# CC2530.net
KiCad netlist of a schematic drawn in Altium Designer
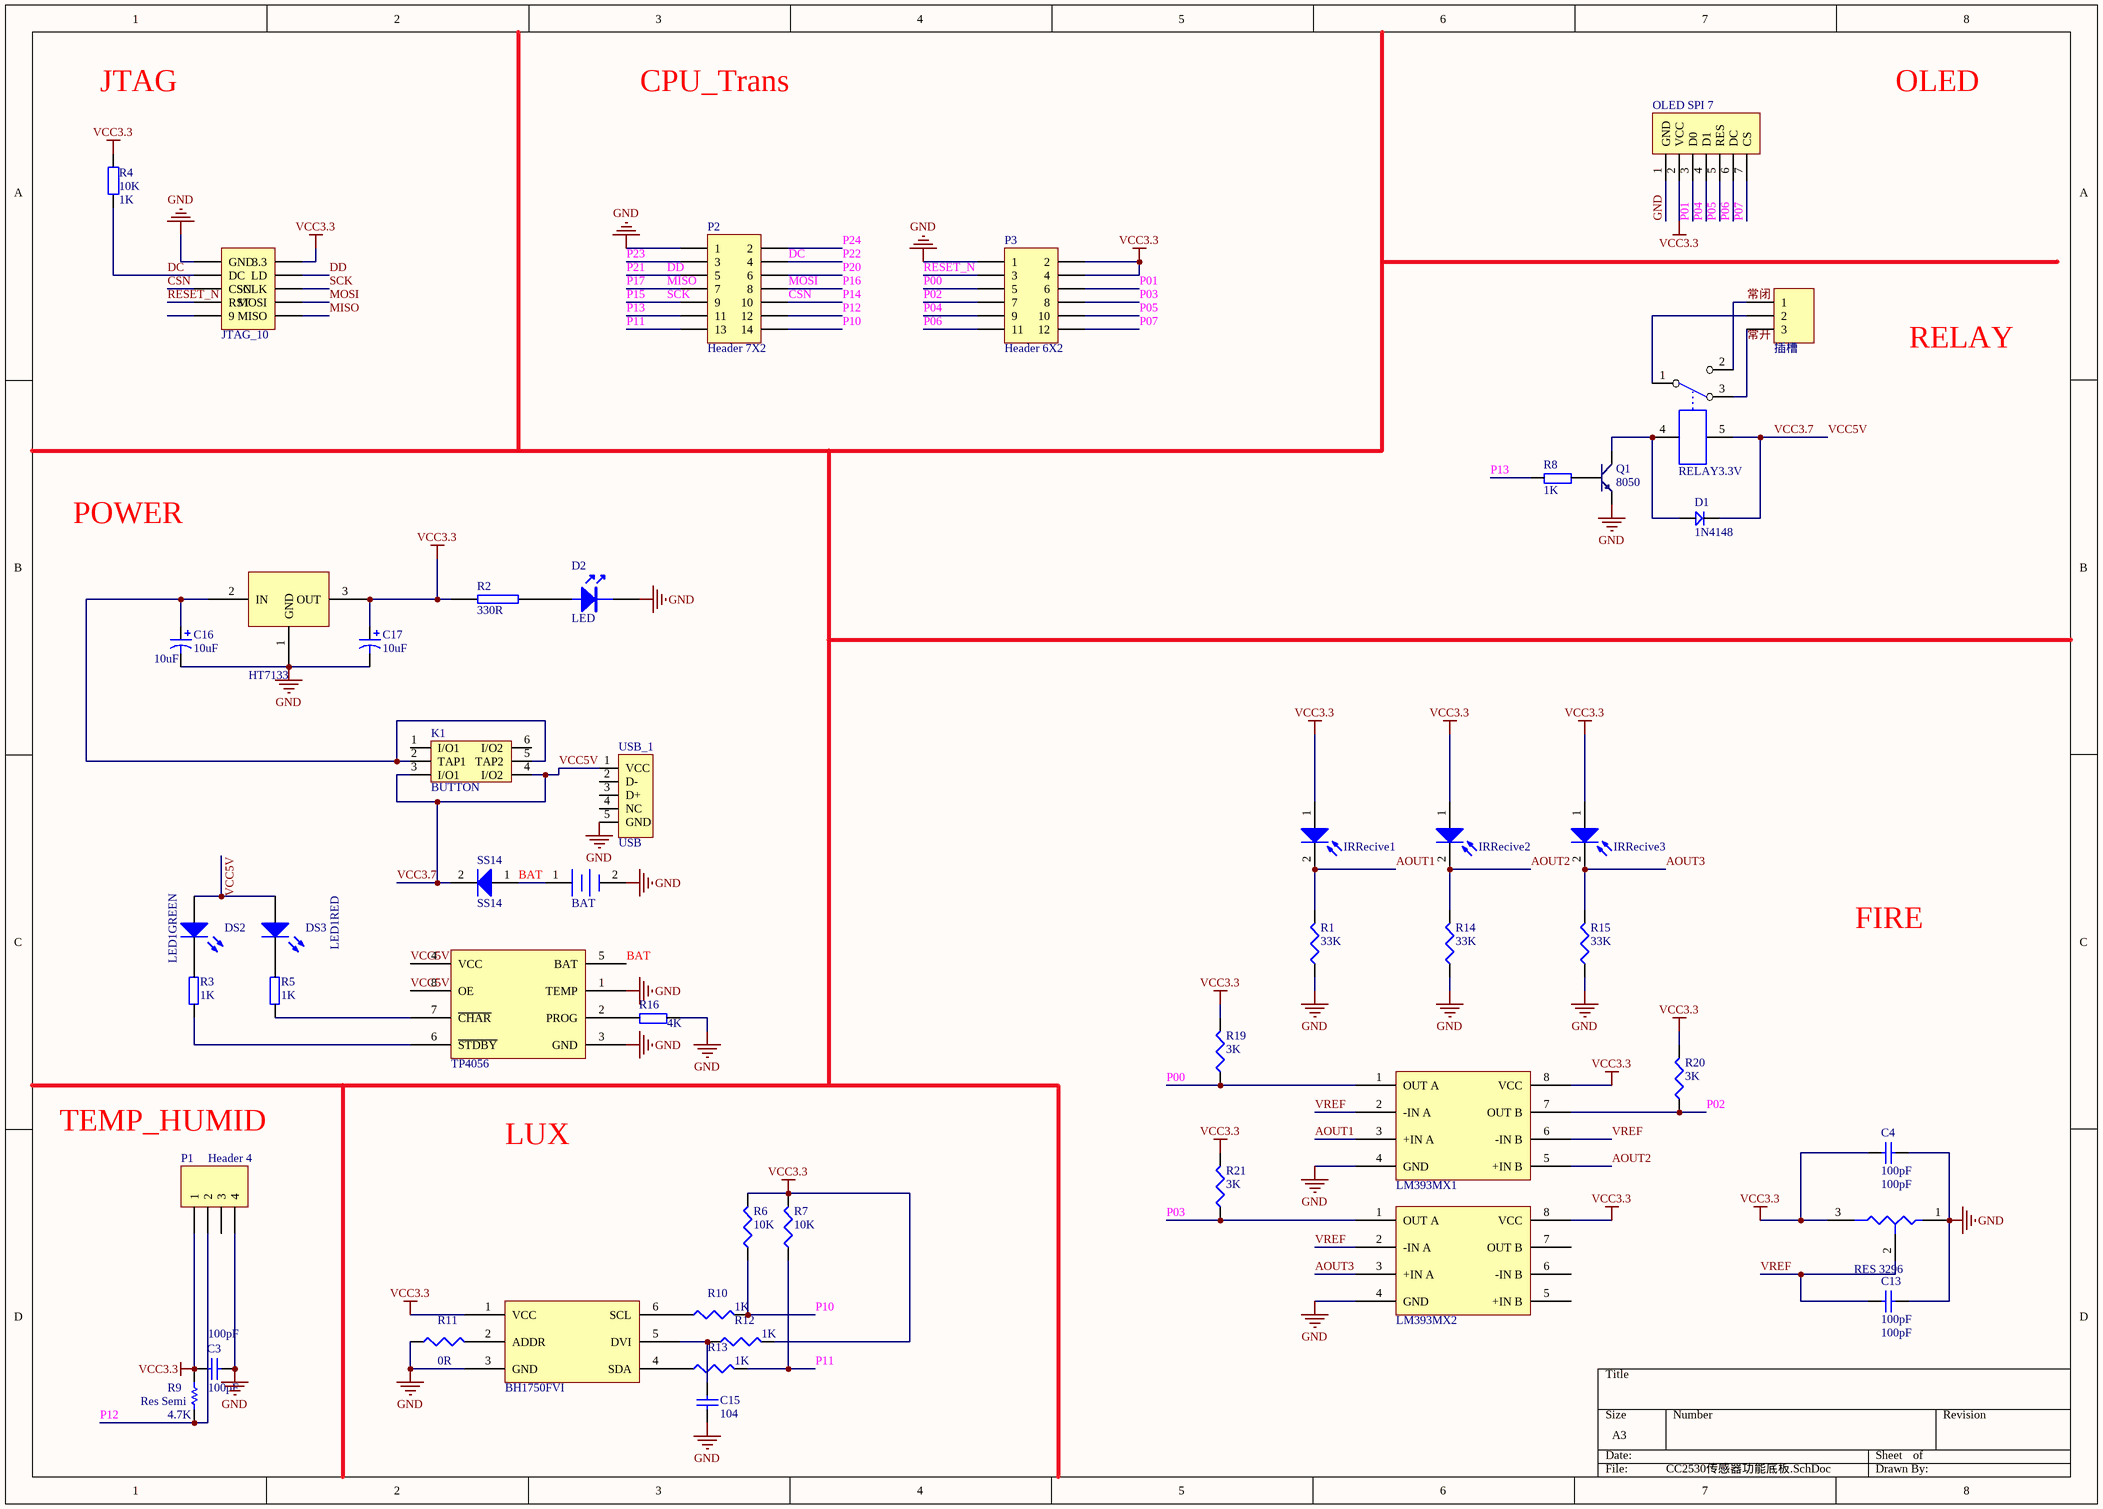
[diagram p0: CC2530传感器功能底板.SchDoc]

(export (version "E")
  (design (tool "Eeschema 10.0.6"))
  (components
    (comp (ref "BAT") (value "BAT") (footprint "BAT") (libsource (lib "my Integrated lib ") (part "BAT")))
    (comp (ref "BH1750FVI")
      (value "BH1750FVI")
      (footprint "BH1750FVI")
      (libsource (lib "my Integrated lib ") (part "BH1750FVI"))
    )
    (comp (ref "C3")
      (value "100pF")
      (footprint "DIODE_SOP")
      (description "Capacitor")
      (fields (field (name "ALTIUM_VALUE") "100pF") (field (name "PUBLISHER") "Altium Limited"))
      (libsource (lib "Miscellaneous Devices") (part "Cap"))
    )
    (comp (ref "C4")
      (value "100pF")
      (footprint "DIODE_SOP")
      (description "Capacitor (Semiconductor SIM Model)")
      (fields (field (name "ALTIUM_VALUE") "100pF") (field (name "PUBLISHER") "Altium Limited"))
      (libsource (lib "Miscellaneous Devices") (part "Cap Semi"))
    )
    (comp (ref "C13")
      (value "100pF")
      (footprint "DIODE_SOP")
      (description "Capacitor (Semiconductor SIM Model)")
      (fields (field (name "ALTIUM_VALUE") "100pF") (field (name "PUBLISHER") "Altium Limited"))
      (libsource (lib "Miscellaneous Devices") (part "Cap Semi"))
    )
    (comp (ref "C15")
      (value "104")
      (footprint "DIODE_SOP")
      (description "Capacitor (Semiconductor SIM Model)")
      (fields (field (name "PUBLISHER") "Altium Limited"))
      (libsource (lib "Miscellaneous Devices") (part "Cap Semi"))
    )
    (comp (ref "C16")
      (value "10uF")
      (footprint "DIODE_SOP")
      (description "Polarized Capacitor (Radial)")
      (fields (field (name "ALTIUM_VALUE") "10uF") (field (name "PUBLISHER") "Altium Limited"))
      (libsource (lib "Miscellaneous Devices") (part "Cap Pol1"))
    )
    (comp (ref "C17")
      (value "10uF")
      (footprint "DIODE_SOP")
      (description "Polarized Capacitor (Radial)")
      (fields (field (name "PUBLISHER") "Altium Limited"))
      (libsource (lib "Miscellaneous Devices") (part "Cap Pol1"))
    )
    (comp (ref "D1") (value "1N4148") (footprint "C1206") (libsource (lib "my Integrated lib ") (part "D")))
    (comp (ref "D2")
      (value "LED")
      (footprint "DIODE_SOP")
      (libsource (lib "Miscellaneous Devices") (part "LED"))
    )
    (comp (ref "DS2")
      (value "LED1GREEN")
      (footprint "SMDLED")
      (description "Typical RED, GREEN, YELLOW, AMBER GaAs LED")
      (fields (field (name "PUBLISHER") "Altium Limited"))
      (libsource (lib "my Integrated lib ") (part "LED2"))
    )
    (comp (ref "DS3")
      (value "LED1RED")
      (footprint "SMDLED")
      (description "Typical RED, GREEN, YELLOW, AMBER GaAs LED")
      (fields (field (name "PUBLISHER") "Altium Limited"))
      (libsource (lib "my Integrated lib ") (part "LED2"))
    )
    (comp (ref "HT7133")
      (value "HT7133")
      (footprint "HT7133")
      (libsource (lib "my Integrated lib ") (part "HT7133"))
    )
    (comp (ref "IRRecive1")
      (value "IRRecive")
      (footprint "IRRecive")
      (libsource (lib "my Integrated lib ") (part "IRRecive"))
    )
    (comp (ref "IRRecive2")
      (value "IRRecive")
      (footprint "IRRecive")
      (libsource (lib "my Integrated lib ") (part "IRRecive"))
    )
    (comp (ref "IRRecive3")
      (value "IRRecive")
      (footprint "IRRecive")
      (libsource (lib "my Integrated lib ") (part "IRRecive"))
    )
    (comp (ref "JTAG_10")
      (value "JTAG_10")
      (footprint "JTAG_10")
      (libsource (lib "my Integrated lib ") (part "JTAG_10"))
    )
    (comp (ref "K1")
      (value "BUTTON")
      (footprint "BTN8.5*8.5")
      (libsource (lib "my Integrated lib ") (part "BUTTON"))
    )
    (comp (ref "LM393MX1")
      (value "LM393MX")
      (footprint "LM393MX")
      (libsource (lib "my Integrated lib ") (part "LM393MX"))
    )
    (comp (ref "LM393MX2")
      (value "LM393MX")
      (footprint "LM393MX")
      (libsource (lib "my Integrated lib ") (part "LM393MX"))
    )
    (comp (ref "OLED SPI 7")
      (value "OLED SPI 7")
      (footprint "OLED SPI 7")
      (libsource (lib "my Integrated lib ") (part "OLED SPI 7"))
    )
    (comp (ref "P1")
      (value "Header 4")
      (footprint "HDR1X4")
      (description "Header, 4-Pin")
      (fields (field (name "PUBLISHER") "Altium Limited"))
      (libsource (lib "Miscellaneous Connectors") (part "Header 4"))
    )
    (comp (ref "P2")
      (value "Header 7X2")
      (footprint "HDR2X7")
      (description "Header, 7-Pin, Dual row")
      (fields (field (name "PUBLISHER") "Altium Limited"))
      (libsource (lib "Miscellaneous Connectors") (part "Header 7X2"))
    )
    (comp (ref "P3")
      (value "Header 6X2")
      (footprint "HDR2X6")
      (description "Header, 6-Pin, Dual row")
      (fields (field (name "PUBLISHER") "Altium Limited"))
      (libsource (lib "Miscellaneous Connectors") (part "Header 6X2"))
    )
    (comp (ref "Q1")
      (value "8050")
      (footprint "SOT-23R")
      (description "8050/BCW846/BCW847")
      (libsource (lib "my Integrated lib ") (part "NPN"))
    )
    (comp (ref "R1")
      (value "33K")
      (footprint "J1-0603")
      (description "Resistor")
      (fields (field (name "Comment") "Res3") (field (name "PUBLISHER") "Altium Limited"))
      (libsource (lib "Miscellaneous Devices") (part "Res3"))
    )
    (comp (ref "R2")
      (value "330R")
      (footprint "J1-0603")
      (libsource (lib "Miscellaneous Devices") (part "RES2"))
    )
    (comp (ref "R3") (value "1K") (footprint "0603P") (libsource (lib "my Integrated lib ") (part "R")))
    (comp (ref "R4")
      (value "10K")
      (footprint "J1-0603")
      (fields (field (name "ALTIUM_VALUE") "1K"))
      (libsource (lib "集成库") (part "res0402"))
    )
    (comp (ref "R5") (value "1K") (footprint "0603P") (libsource (lib "my Integrated lib ") (part "R")))
    (comp (ref "R6")
      (value "10K")
      (footprint "J1-0603")
      (description "Resistor")
      (fields (field (name "Comment") "Res3") (field (name "PUBLISHER") "Altium Limited"))
      (libsource (lib "Miscellaneous Devices") (part "Res3"))
    )
    (comp (ref "R7")
      (value "10K")
      (footprint "J1-0603")
      (description "Resistor")
      (fields (field (name "Comment") "Res3") (field (name "PUBLISHER") "Altium Limited"))
      (libsource (lib "Miscellaneous Devices") (part "Res3"))
    )
    (comp (ref "R8") (value "1K") (footprint "J1-0603") (libsource (lib "my Integrated lib ") (part "R")))
    (comp (ref "R9")
      (value "Res Semi")
      (footprint "J1-0603")
      (description "Semiconductor Resistor")
      (fields (field (name "ALTIUM_VALUE") "4.7K") (field (name "PUBLISHER") "Altium Limited"))
      (libsource (lib "Miscellaneous Devices") (part "Res Semi"))
    )
    (comp (ref "R10")
      (value "1K")
      (footprint "J1-0603")
      (description "Resistor")
      (fields (field (name "Comment") "Res3") (field (name "PUBLISHER") "Altium Limited"))
      (libsource (lib "Miscellaneous Devices") (part "Res3"))
    )
    (comp (ref "R11")
      (value "0R")
      (footprint "J1-0603")
      (description "Resistor")
      (fields (field (name "Comment") "Res3") (field (name "PUBLISHER") "Altium Limited"))
      (libsource (lib "Miscellaneous Devices") (part "Res3"))
    )
    (comp (ref "R12")
      (value "1K")
      (footprint "J1-0603")
      (description "Resistor")
      (fields (field (name "Comment") "Res3") (field (name "PUBLISHER") "Altium Limited"))
      (libsource (lib "Miscellaneous Devices") (part "Res3"))
    )
    (comp (ref "R13")
      (value "1K")
      (footprint "J1-0603")
      (description "Resistor")
      (fields (field (name "Comment") "Res3") (field (name "PUBLISHER") "Altium Limited"))
      (libsource (lib "Miscellaneous Devices") (part "Res3"))
    )
    (comp (ref "R14")
      (value "33K")
      (footprint "J1-0603")
      (description "Resistor")
      (fields (field (name "Comment") "Res3") (field (name "PUBLISHER") "Altium Limited"))
      (libsource (lib "Miscellaneous Devices") (part "Res3"))
    )
    (comp (ref "R15")
      (value "33K")
      (footprint "J1-0603")
      (description "Resistor")
      (fields (field (name "Comment") "Res3") (field (name "PUBLISHER") "Altium Limited"))
      (libsource (lib "Miscellaneous Devices") (part "Res3"))
    )
    (comp (ref "R16") (value "4K") (footprint "0603P") (libsource (lib "my Integrated lib ") (part "R")))
    (comp (ref "R19")
      (value "3K")
      (footprint "J1-0603")
      (description "Resistor")
      (fields (field (name "Comment") "Res3") (field (name "PUBLISHER") "Altium Limited"))
      (libsource (lib "Miscellaneous Devices") (part "Res3"))
    )
    (comp (ref "R20")
      (value "3K")
      (footprint "J1-0603")
      (description "Resistor")
      (fields (field (name "Comment") "Res3") (field (name "PUBLISHER") "Altium Limited"))
      (libsource (lib "Miscellaneous Devices") (part "Res3"))
    )
    (comp (ref "R21")
      (value "3K")
      (footprint "J1-0603")
      (description "Resistor")
      (fields (field (name "Comment") "Res3") (field (name "PUBLISHER") "Altium Limited"))
      (libsource (lib "Miscellaneous Devices") (part "Res3"))
    )
    (comp (ref "RELAY3.3V")
      (value "RELAY3.3V")
      (footprint "RELAY3.3V")
      (libsource (lib "my Integrated lib ") (part "RELAY3.3V"))
    )
    (comp (ref "RES 3296")
      (value "RES 3296")
      (footprint "RES 3296")
      (libsource (lib "my Integrated lib ") (part "RES 3296"))
    )
    (comp (ref "SS14")
      (value "SS14")
      (footprint "IN4007")
      (libsource (lib "my Integrated lib ") (part "IN4007"))
    )
    (comp (ref "TP4056")
      (value "TP4056")
      (footprint "TP4056")
      (libsource (lib "my Integrated lib ") (part "TP4056"))
    )
    (comp (ref "USB_1")
      (value "USB")
      (footprint "USB/SM0.8-6H5")
      (libsource (lib "MiniSTM32 V2.0封装库") (part "USB5"))
    )
    (comp (ref "插槽") (value "插槽") (footprint "杜邦线插槽") (libsource (lib "my Integrated lib ") (part "插槽")))
  )
  (nets
    (net (code "1") (name "/AOUT1") (class "Default")
      (node (ref "IRRecive1") (pin "2") (pinfunction "K_2") (pintype "passive"))
      (node (ref "LM393MX1") (pin "3") (pinfunction "+IN_A_3") (pintype "passive"))
      (node (ref "R1") (pin "2") (pinfunction "2_2") (pintype "passive"))
    )
    (net (code "2") (name "/AOUT2") (class "Default")
      (node (ref "IRRecive2") (pin "2") (pinfunction "K_2") (pintype "passive"))
      (node (ref "LM393MX1") (pin "5") (pinfunction "+IN_B_5") (pintype "passive"))
      (node (ref "R14") (pin "2") (pinfunction "2_2") (pintype "passive"))
    )
    (net (code "3") (name "/AOUT3") (class "Default")
      (node (ref "IRRecive3") (pin "2") (pinfunction "K_2") (pintype "passive"))
      (node (ref "LM393MX2") (pin "3") (pinfunction "+IN_A_3") (pintype "passive"))
      (node (ref "R15") (pin "2") (pinfunction "2_2") (pintype "passive"))
    )
    (net (code "4") (name "/BAT") (class "Default")
      (node (ref "BAT") (pin "1") (pinfunction "+_1") (pintype "passive"))
      (node (ref "SS14") (pin "1") (pinfunction "A_1") (pintype "passive"))
      (node (ref "TP4056") (pin "5") (pinfunction "BAT_5") (pintype "passive"))
    )
    (net (code "5") (name "/CSN") (class "Default")
      (node (ref "JTAG_10") (pin "5") (pinfunction "CSN_5") (pintype "passive"))
      (node (ref "P2") (pin "10") (pinfunction "10_10") (pintype "passive"))
    )
    (net (code "6") (name "/DC") (class "Default")
      (node (ref "JTAG_10") (pin "3") (pinfunction "DC_3") (pintype "passive"))
      (node (ref "P2") (pin "4") (pinfunction "4_4") (pintype "passive"))
      (node (ref "R4") (pin "1") (pinfunction "1_1") (pintype "passive"))
    )
    (net (code "7") (name "/DD") (class "Default")
      (node (ref "JTAG_10") (pin "4") (pinfunction "LD_4") (pintype "passive"))
      (node (ref "P2") (pin "5") (pinfunction "5_5") (pintype "passive"))
    )
    (net (code "8") (name "/MISO") (class "Default")
      (node (ref "JTAG_10") (pin "10") (pinfunction "MISO_10") (pintype "passive"))
      (node (ref "P2") (pin "7") (pinfunction "7_7") (pintype "passive"))
    )
    (net (code "9") (name "/MOSI") (class "Default")
      (node (ref "JTAG_10") (pin "8") (pinfunction "MOSI_8") (pintype "passive"))
      (node (ref "P2") (pin "8") (pinfunction "8_8") (pintype "passive"))
    )
    (net (code "10") (name "/P00") (class "Default")
      (node (ref "LM393MX1") (pin "1") (pinfunction "OUT_A_1") (pintype "passive"))
      (node (ref "P3") (pin "5") (pinfunction "5_5") (pintype "passive"))
      (node (ref "R19") (pin "1") (pinfunction "1_1") (pintype "passive"))
    )
    (net (code "11") (name "/P01") (class "Default")
      (node (ref "OLED SPI 7") (pin "3") (pinfunction "D0_3") (pintype "passive"))
      (node (ref "P3") (pin "6") (pinfunction "6_6") (pintype "passive"))
    )
    (net (code "12") (name "/P02") (class "Default")
      (node (ref "LM393MX1") (pin "7") (pinfunction "OUT_B_7") (pintype "passive"))
      (node (ref "P3") (pin "7") (pinfunction "7_7") (pintype "passive"))
      (node (ref "R20") (pin "1") (pinfunction "1_1") (pintype "passive"))
    )
    (net (code "13") (name "/P03") (class "Default")
      (node (ref "LM393MX2") (pin "1") (pinfunction "OUT_A_1") (pintype "passive"))
      (node (ref "P3") (pin "8") (pinfunction "8_8") (pintype "passive"))
      (node (ref "R21") (pin "1") (pinfunction "1_1") (pintype "passive"))
    )
    (net (code "14") (name "/P04") (class "Default")
      (node (ref "OLED SPI 7") (pin "4") (pinfunction "D1_4") (pintype "passive"))
      (node (ref "P3") (pin "9") (pinfunction "9_9") (pintype "passive"))
    )
    (net (code "15") (name "/P05") (class "Default")
      (node (ref "OLED SPI 7") (pin "5") (pinfunction "RES_5") (pintype "passive"))
      (node (ref "P3") (pin "10") (pinfunction "10_10") (pintype "passive"))
    )
    (net (code "16") (name "/P06") (class "Default")
      (node (ref "OLED SPI 7") (pin "6") (pinfunction "DC_6") (pintype "passive"))
      (node (ref "P3") (pin "11") (pinfunction "11_11") (pintype "passive"))
    )
    (net (code "17") (name "/P07") (class "Default")
      (node (ref "OLED SPI 7") (pin "7") (pinfunction "CS_7") (pintype "passive"))
      (node (ref "P3") (pin "12") (pinfunction "12_12") (pintype "passive"))
    )
    (net (code "18") (name "/P10") (class "Default")
      (node (ref "P2") (pin "14") (pinfunction "14_14") (pintype "passive"))
      (node (ref "R10") (pin "2") (pinfunction "2_2") (pintype "passive"))
      (node (ref "R6") (pin "1") (pinfunction "1_1") (pintype "passive"))
    )
    (net (code "19") (name "/P11") (class "Default")
      (node (ref "P2") (pin "13") (pinfunction "13_13") (pintype "passive"))
      (node (ref "R13") (pin "2") (pinfunction "2_2") (pintype "passive"))
      (node (ref "R7") (pin "1") (pinfunction "1_1") (pintype "passive"))
    )
    (net (code "20") (name "/P12") (class "Default")
      (node (ref "P1") (pin "2") (pinfunction "2_2") (pintype "passive"))
      (node (ref "P2") (pin "12") (pinfunction "12_12") (pintype "passive"))
      (node (ref "R9") (pin "1") (pinfunction "1_1") (pintype "passive"))
    )
    (net (code "21") (name "/P13") (class "Default")
      (node (ref "P2") (pin "11") (pinfunction "11_11") (pintype "passive"))
      (node (ref "R8") (pin "1") (pintype "passive"))
    )
    (net (code "22") (name "/P15") (class "Default")
      (node (ref "JTAG_10") (pin "6") (pinfunction "SCLK_6") (pintype "passive"))
      (node (ref "P2") (pin "9") (pinfunction "9_9") (pintype "passive"))
    )
    (net (code "23") (name "/P20") (class "Default")
      (node (ref "P2") (pin "6") (pinfunction "6_6") (pintype "passive"))
    )
    (net (code "24") (name "/P23") (class "Default")
      (node (ref "P2") (pin "3") (pinfunction "3_3") (pintype "passive"))
    )
    (net (code "25") (name "/P24") (class "Default")
      (node (ref "P2") (pin "2") (pinfunction "2_2") (pintype "passive"))
    )
    (net (code "26") (name "/RESET_N") (class "Default")
      (node (ref "JTAG_10") (pin "7") (pinfunction "RST_7") (pintype "passive"))
      (node (ref "P3") (pin "3") (pinfunction "3_3") (pintype "passive"))
    )
    (net (code "27") (name "/VCC3.7") (class "Default")
      (node (ref "D1") (pin "2") (pintype "passive"))
      (node (ref "DS2") (pin "1") (pinfunction "A_1") (pintype "passive"))
      (node (ref "DS3") (pin "1") (pinfunction "A_1") (pintype "passive"))
      (node (ref "K1") (pin "3") (pinfunction "I/O1_3") (pintype "passive"))
      (node (ref "K1") (pin "4") (pinfunction "I/O2_4") (pintype "passive"))
      (node (ref "RELAY3.3V") (pin "5") (pinfunction "5_5") (pintype "passive"))
      (node (ref "SS14") (pin "2") (pinfunction "K_2") (pintype "passive"))
      (node (ref "TP4056") (pin "4") (pinfunction "VCC_4") (pintype "passive"))
      (node (ref "TP4056") (pin "8") (pinfunction "OE_8") (pintype "passive"))
      (node (ref "USB_1") (pin "1") (pinfunction "VCC_1") (pintype "passive"))
    )
    (net (code "28") (name "/VREF") (class "Default")
      (node (ref "C13") (pin "1") (pinfunction "1_1") (pintype "passive"))
      (node (ref "LM393MX1") (pin "2") (pinfunction "-IN_A_2") (pintype "passive"))
      (node (ref "LM393MX1") (pin "6") (pinfunction "-IN_B_6") (pintype "passive"))
      (node (ref "LM393MX2") (pin "2") (pinfunction "-IN_A_2") (pintype "passive"))
      (node (ref "RES 3296") (pin "2") (pinfunction "TAP_2") (pintype "passive"))
    )
    (net (code "29") (name "/常开") (class "Default")
      (node (ref "RELAY3.3V") (pin "3") (pinfunction "3_3") (pintype "passive"))
      (node (ref "插槽") (pin "3") (pinfunction "3_3") (pintype "passive"))
    )
    (net (code "30") (name "/常闭") (class "Default")
      (node (ref "RELAY3.3V") (pin "2") (pinfunction "2_2") (pintype "passive"))
      (node (ref "插槽") (pin "1") (pinfunction "1_1") (pintype "passive"))
    )
    (net (code "31") (name "GND") (class "Default")
      (node (ref "BAT") (pin "2") (pinfunction "-_2") (pintype "passive"))
      (node (ref "BH1750FVI") (pin "3") (pinfunction "GND_3") (pintype "passive"))
      (node (ref "C13") (pin "2") (pinfunction "2_2") (pintype "passive"))
      (node (ref "C15") (pin "1") (pinfunction "1_1") (pintype "passive"))
      (node (ref "C16") (pin "2") (pinfunction "2_2") (pintype "passive"))
      (node (ref "C17") (pin "2") (pinfunction "2_2") (pintype "passive"))
      (node (ref "C3") (pin "2") (pinfunction "2_2") (pintype "passive"))
      (node (ref "C4") (pin "2") (pinfunction "2_2") (pintype "passive"))
      (node (ref "D2") (pin "K") (pinfunction "2_K") (pintype "passive"))
      (node (ref "HT7133") (pin "1") (pinfunction "GND_1") (pintype "passive"))
      (node (ref "JTAG_10") (pin "1") (pinfunction "GND_1") (pintype "passive"))
      (node (ref "LM393MX1") (pin "4") (pinfunction "GND_4") (pintype "passive"))
      (node (ref "LM393MX2") (pin "4") (pinfunction "GND_4") (pintype "passive"))
      (node (ref "OLED SPI 7") (pin "1") (pinfunction "GND_1") (pintype "passive"))
      (node (ref "P1") (pin "4") (pinfunction "4_4") (pintype "passive"))
      (node (ref "P2") (pin "1") (pinfunction "1_1") (pintype "passive"))
      (node (ref "P3") (pin "1") (pinfunction "1_1") (pintype "passive"))
      (node (ref "Q1") (pin "1") (pinfunction "E_1") (pintype "passive"))
      (node (ref "R1") (pin "1") (pinfunction "1_1") (pintype "passive"))
      (node (ref "R11") (pin "1") (pinfunction "1_1") (pintype "passive"))
      (node (ref "R14") (pin "1") (pinfunction "1_1") (pintype "passive"))
      (node (ref "R15") (pin "1") (pinfunction "1_1") (pintype "passive"))
      (node (ref "R16") (pin "2") (pintype "passive"))
      (node (ref "RES 3296") (pin "1") (pinfunction "A_1") (pintype "passive"))
      (node (ref "TP4056") (pin "1") (pinfunction "TEMP_1") (pintype "passive"))
      (node (ref "TP4056") (pin "3") (pinfunction "GND_3") (pintype "passive"))
      (node (ref "USB_1") (pin "5") (pinfunction "GND_5") (pintype "passive"))
    )
    (net (code "32") (name "Net-(BH1750FVI-ADDR)") (class "Default")
      (node (ref "BH1750FVI") (pin "2") (pinfunction "ADDR_2") (pintype "passive"))
      (node (ref "R11") (pin "2") (pinfunction "2_2") (pintype "passive"))
    )
    (net (code "33") (name "Net-(BH1750FVI-DVI)") (class "Default")
      (node (ref "BH1750FVI") (pin "5") (pinfunction "DVI_5") (pintype "passive"))
      (node (ref "C15") (pin "2") (pinfunction "2_2") (pintype "passive"))
      (node (ref "R12") (pin "1") (pinfunction "1_1") (pintype "passive"))
    )
    (net (code "34") (name "Net-(BH1750FVI-SCL)") (class "Default")
      (node (ref "BH1750FVI") (pin "6") (pinfunction "SCL_6") (pintype "passive"))
      (node (ref "R10") (pin "1") (pinfunction "1_1") (pintype "passive"))
    )
    (net (code "35") (name "Net-(BH1750FVI-SDA)") (class "Default")
      (node (ref "BH1750FVI") (pin "4") (pinfunction "SDA_4") (pintype "passive"))
      (node (ref "R13") (pin "1") (pinfunction "1_1") (pintype "passive"))
    )
    (net (code "36") (name "Net-(D2-1)") (class "Default")
      (node (ref "D2") (pin "A") (pinfunction "1_A") (pintype "passive"))
      (node (ref "R2") (pin "1") (pinfunction "1_1") (pintype "passive"))
    )
    (net (code "37") (name "Net-(DS2-K)") (class "Default")
      (node (ref "DS2") (pin "2") (pinfunction "K_2") (pintype "passive"))
      (node (ref "R3") (pin "1") (pintype "passive"))
    )
    (net (code "38") (name "Net-(DS3-K)") (class "Default")
      (node (ref "DS3") (pin "2") (pinfunction "K_2") (pintype "passive"))
      (node (ref "R5") (pin "1") (pintype "passive"))
    )
    (net (code "39") (name "Net-(HT7133-IN)") (class "Default")
      (node (ref "C16") (pin "1") (pinfunction "1_1") (pintype "passive"))
      (node (ref "HT7133") (pin "2") (pinfunction "IN_2") (pintype "passive"))
      (node (ref "K1") (pin "2") (pinfunction "TAP1_2") (pintype "passive"))
      (node (ref "K1") (pin "5") (pinfunction "TAP2_5") (pintype "passive"))
    )
    (net (code "40") (name "Net-(Q1-B)") (class "Default")
      (node (ref "Q1") (pin "2") (pinfunction "B_2") (pintype "passive"))
      (node (ref "R8") (pin "2") (pintype "passive"))
    )
    (net (code "41") (name "Net-(Q1-C)") (class "Default")
      (node (ref "D1") (pin "1") (pintype "passive"))
      (node (ref "Q1") (pin "3") (pinfunction "C_3") (pintype "passive"))
      (node (ref "RELAY3.3V") (pin "4") (pinfunction "4_4") (pintype "passive"))
    )
    (net (code "42") (name "Net-(RELAY3.3V-Pad1)") (class "Default")
      (node (ref "RELAY3.3V") (pin "1") (pinfunction "1_1") (pintype "passive"))
      (node (ref "插槽") (pin "2") (pinfunction "2_2") (pintype "passive"))
    )
    (net (code "43") (name "Net-(TP4056-PROG)") (class "Default")
      (node (ref "R16") (pin "1") (pintype "passive"))
      (node (ref "TP4056") (pin "2") (pinfunction "PROG_2") (pintype "passive"))
    )
    (net (code "44") (name "Net-(TP4056-~{CHAR})") (class "Default")
      (node (ref "R5") (pin "2") (pintype "passive"))
      (node (ref "TP4056") (pin "7") (pinfunction "~{CHAR}_7") (pintype "passive"))
    )
    (net (code "45") (name "Net-(TP4056-~{STDBY})") (class "Default")
      (node (ref "R3") (pin "2") (pintype "passive"))
      (node (ref "TP4056") (pin "6") (pinfunction "~{STDBY}_6") (pintype "passive"))
    )
    (net (code "46") (name "VCC3.3") (class "Default")
      (node (ref "BH1750FVI") (pin "1") (pinfunction "VCC_1") (pintype "passive"))
      (node (ref "C17") (pin "1") (pinfunction "1_1") (pintype "passive"))
      (node (ref "C3") (pin "1") (pinfunction "1_1") (pintype "passive"))
      (node (ref "C4") (pin "1") (pinfunction "1_1") (pintype "passive"))
      (node (ref "HT7133") (pin "3") (pinfunction "OUT_3") (pintype "passive"))
      (node (ref "IRRecive1") (pin "1") (pinfunction "A_1") (pintype "passive"))
      (node (ref "IRRecive2") (pin "1") (pinfunction "A_1") (pintype "passive"))
      (node (ref "IRRecive3") (pin "1") (pinfunction "A_1") (pintype "passive"))
      (node (ref "JTAG_10") (pin "2") (pinfunction "3.3_2") (pintype "passive"))
      (node (ref "LM393MX1") (pin "8") (pinfunction "VCC_8") (pintype "passive"))
      (node (ref "LM393MX2") (pin "8") (pinfunction "VCC_8") (pintype "passive"))
      (node (ref "OLED SPI 7") (pin "2") (pinfunction "VCC_2") (pintype "passive"))
      (node (ref "P1") (pin "1") (pinfunction "1_1") (pintype "passive"))
      (node (ref "P3") (pin "2") (pinfunction "2_2") (pintype "passive"))
      (node (ref "P3") (pin "4") (pinfunction "4_4") (pintype "passive"))
      (node (ref "R12") (pin "2") (pinfunction "2_2") (pintype "passive"))
      (node (ref "R19") (pin "2") (pinfunction "2_2") (pintype "passive"))
      (node (ref "R2") (pin "2") (pinfunction "2_2") (pintype "passive"))
      (node (ref "R20") (pin "2") (pinfunction "2_2") (pintype "passive"))
      (node (ref "R21") (pin "2") (pinfunction "2_2") (pintype "passive"))
      (node (ref "R4") (pin "2") (pinfunction "2_2") (pintype "passive"))
      (node (ref "R6") (pin "2") (pinfunction "2_2") (pintype "passive"))
      (node (ref "R7") (pin "2") (pinfunction "2_2") (pintype "passive"))
      (node (ref "R9") (pin "2") (pinfunction "2_2") (pintype "passive"))
      (node (ref "RES 3296") (pin "3") (pinfunction "B_3") (pintype "passive"))
    )
    (net (code "47") (name "unconnected-(JTAG_10-Pad9)") (class "Default")
      (node (ref "JTAG_10") (pin "9") (pinfunction "9_9") (pintype "passive"))
    )
    (net (code "48") (name "unconnected-(K1-I{slash}O1-Pad1)") (class "Default")
      (node (ref "K1") (pin "1") (pinfunction "I/O1_1") (pintype "passive"))
    )
    (net (code "49") (name "unconnected-(K1-I{slash}O2-Pad6)") (class "Default")
      (node (ref "K1") (pin "6") (pinfunction "I/O2_6") (pintype "passive"))
    )
    (net (code "50") (name "unconnected-(LM393MX2-+IN_B-Pad5)") (class "Default")
      (node (ref "LM393MX2") (pin "5") (pinfunction "+IN_B_5") (pintype "passive"))
    )
    (net (code "51") (name "unconnected-(LM393MX2--IN_B-Pad6)") (class "Default")
      (node (ref "LM393MX2") (pin "6") (pinfunction "-IN_B_6") (pintype "passive"))
    )
    (net (code "52") (name "unconnected-(LM393MX2-OUT_B-Pad7)") (class "Default")
      (node (ref "LM393MX2") (pin "7") (pinfunction "OUT_B_7") (pintype "passive"))
    )
    (net (code "53") (name "unconnected-(P1-Pad3)") (class "Default")
      (node (ref "P1") (pin "3") (pinfunction "3_3") (pintype "passive"))
    )
    (net (code "54") (name "unconnected-(USB_1-D+-Pad3)") (class "Default")
      (node (ref "USB_1") (pin "3") (pinfunction "D+_3") (pintype "passive"))
    )
    (net (code "55") (name "unconnected-(USB_1-D--Pad2)") (class "Default")
      (node (ref "USB_1") (pin "2") (pinfunction "D-_2") (pintype "passive"))
    )
    (net (code "56") (name "unconnected-(USB_1-NC-Pad4)") (class "Default")
      (node (ref "USB_1") (pin "4") (pinfunction "NC_4") (pintype "passive"))
    )
  )
)
